# BQ76952_AFE.net
KiCad netlist of a schematic drawn in Altium Designer
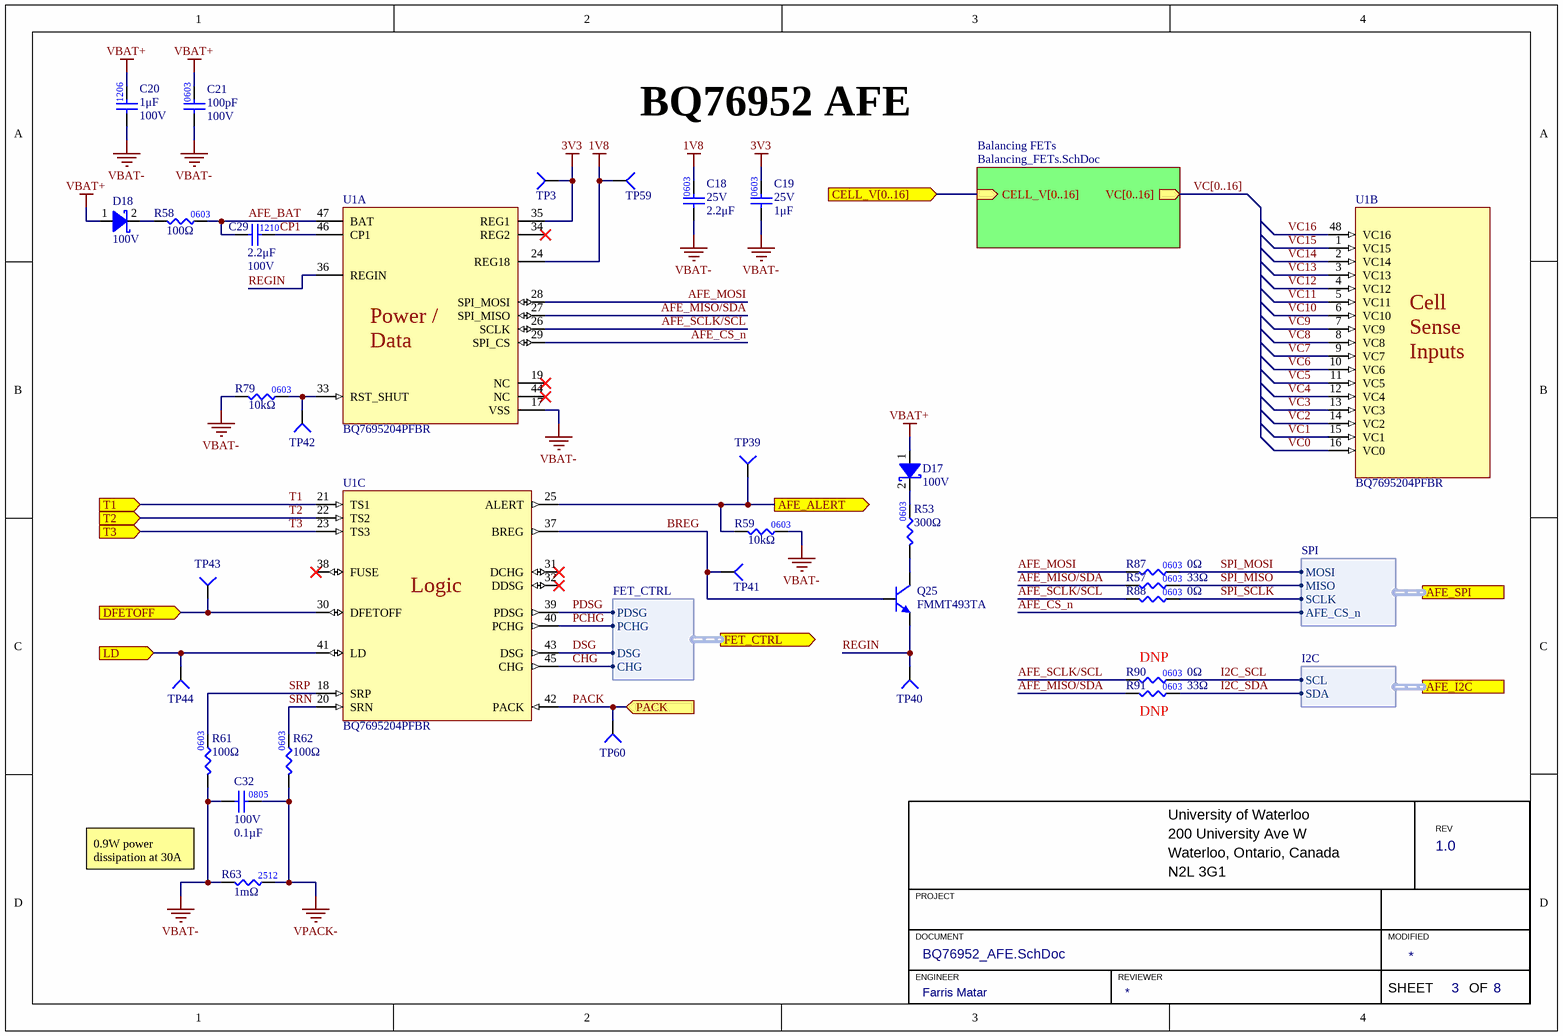
[diagram p0: BQ76952_AFE.SchDoc]

(export (version "E")
  (design (tool "Eeschema 10.0.6"))
  (components
    (comp (ref "C18")
      (value "2.2μF")
      (footprint "CAP0603")
      (description "CAP CER 2.2UF 25V X5R 0603")
      (fields (field (name "VOLTAGE RATING") "25V") (field (name "Comment") "CAP_2.2uF_25V_0603"))
      (libsource (lib "Personal_Schematic_Library_2022") (part "CAP_2.2uF_25V_0603"))
    )
    (comp (ref "C19")
      (value "1μF")
      (footprint "CAP0603")
      (description "CAP CER 1UF 25V X5R 0603")
      (fields (field (name "VOLTAGE RATING") "25V") (field (name "Comment") "CAP_1uF_25V_0603"))
      (libsource (lib "Personal_Schematic_Library_2022") (part "CAP_1uF_25V_0603"))
    )
    (comp (ref "C20")
      (value "1μF")
      (footprint "CAP1206")
      (description "CAP CER 1UF 100V X7R 1206")
      (fields (field (name "VOLTAGE RATING") "100V") (field (name "Comment") "CAP_1uF_100V_1206"))
      (libsource (lib "Personal_Schematic_Library_2022") (part "CAP_1uF_100V_1206"))
    )
    (comp (ref "C21")
      (value "100pF")
      (footprint "CAP2012")
      (description "CAP CER 100PF 100V X7R 0603")
      (fields (field (name "VOLTAGE RATING") "100V") (field (name "Comment") "CAP_100pF_100V_0603"))
      (libsource (lib "Personal_Schematic_Library_2022") (part "CAP_100pF_100V_0603"))
    )
    (comp (ref "C29")
      (value "2.2μF")
      (footprint "CAP1210")
      (description "CAP CER 2.2UF 100V X7R 1210")
      (fields (field (name "VOLTAGE RATING") "100V") (field (name "Comment") "CAP_2.2uF_100V_1210"))
      (libsource (lib "Personal_Schematic_Library_2022") (part "CAP_2.2uF_100V_1210"))
    )
    (comp (ref "C32")
      (value "0.1µF")
      (footprint "CAP0805")
      (description "CAP CER 0.1UF 100V X7R 0805")
      (fields (field (name "VOLTAGE RATING") "100V") (field (name "Comment") "CAP_0.1uF_100V_0805"))
      (libsource (lib "Personal_Schematic_Library_2022") (part "CAP_0.1uF_100V_0805"))
    )
    (comp (ref "D17")
      (value "DIO_SCHOTTKY_100V_1A")
      (footprint "SOD-123_FLAT")
      (description "DIODE SCHOTTKY 100V 1A SOD-123F")
      (fields (field (name "VR (MAX)") "100V"))
      (libsource (lib "Personal_Schematic_Library_2022") (part "DIO_SCHOTTKY_100V_1A"))
    )
    (comp (ref "D18")
      (value "DIO_SCHOTTKY_100V_1A")
      (footprint "SOD-123_FLAT")
      (description "DIODE SCHOTTKY 100V 1A SOD-123F")
      (fields (field (name "VR (MAX)") "100V"))
      (libsource (lib "Personal_Schematic_Library_2022") (part "DIO_SCHOTTKY_100V_1A"))
    )
    (comp (ref "Q25")
      (value "NPN_100V_1A")
      (footprint "SOT23-3")
      (description "TRANS NPN 100V 1A SOT23-3")
      (fields (field (name "MANUFACTURER PART NUMBER 1") "FMMT493TA"))
      (libsource (lib "Personal_Schematic_Library_2022") (part "NPN_100V_1A"))
    )
    (comp (ref "R53")
      (value "300Ω")
      (footprint "RES0603")
      (description "RES 200 OHM 1% 1/10W 0603")
      (fields (field (name "TOLERANCE") "1%") (field (name "Comment") "RES_300Ω_0603_1%"))
      (libsource (lib "Personal_Schematic_Library_2022") (part "RES_300Ω_0603_1%"))
    )
    (comp (ref "R57")
      (value "33Ω")
      (footprint "RES0603")
      (description "RES 33 OHM 1% 1/10W 0603")
      (fields (field (name "Comment") "RES_33Ω_0603_1%"))
      (libsource (lib "Personal_Schematic_Library_2022") (part "RES_33Ω_0603_1%"))
    )
    (comp (ref "R58")
      (value "100Ω")
      (footprint "RES0603")
      (description "RES 100 OHM 1% 1/10W 0603")
      (fields (field (name "Comment") "RES_100Ω_0603_1%"))
      (libsource (lib "Personal_Schematic_Library_2022") (part "RES_100Ω_0603_1%"))
    )
    (comp (ref "R59")
      (value "10kΩ")
      (footprint "RES0603")
      (description "RES 10K OHM 1% 1/8W 0603")
      (fields (field (name "Comment") "RES_10kΩ_0603_1%"))
      (libsource (lib "Personal_Schematic_Library_2022") (part "RES_10kΩ_0603_1%"))
    )
    (comp (ref "R61")
      (value "100Ω")
      (footprint "RES0603")
      (description "RES 100 OHM 1% 1/10W 0603")
      (fields (field (name "Comment") "RES_100Ω_0603_1%"))
      (libsource (lib "Personal_Schematic_Library_2022") (part "RES_100Ω_0603_1%"))
    )
    (comp (ref "R62")
      (value "100Ω")
      (footprint "RES0603")
      (description "RES 100 OHM 1% 1/10W 0603")
      (fields (field (name "Comment") "RES_100Ω_0603_1%"))
      (libsource (lib "Personal_Schematic_Library_2022") (part "RES_100Ω_0603_1%"))
    )
    (comp (ref "R63")
      (value "1mΩ")
      (footprint "RESC6532X75N")
      (description "RES 1 mOHM 1% 3W 2512")
      (fields (field (name "Comment") "RES_1mΩ_2512_1%"))
      (libsource (lib "Personal_Schematic_Library_2022") (part "RES_1mΩ_2512_1%"))
    )
    (comp (ref "R79")
      (value "10kΩ")
      (footprint "RES0603")
      (description "RES 10K OHM 1% 1/8W 0603")
      (fields (field (name "Comment") "RES_10kΩ_0603_1%"))
      (libsource (lib "Personal_Schematic_Library_2022") (part "RES_10kΩ_0603_1%"))
    )
    (comp (ref "R87")
      (value "0Ω")
      (footprint "RES0603")
      (description "RES 0 OHM JUMPER 1/10W 0603")
      (fields (field (name "Comment") "RES_0Ω_0603"))
      (libsource (lib "Personal_Schematic_Library_2022") (part "RES_0Ω_0603"))
    )
    (comp (ref "R88")
      (value "0Ω")
      (footprint "RES0603")
      (description "RES 0 OHM JUMPER 1/10W 0603")
      (fields (field (name "Comment") "RES_0Ω_0603"))
      (libsource (lib "Personal_Schematic_Library_2022") (part "RES_0Ω_0603"))
    )
    (comp (ref "R90")
      (value "0Ω")
      (footprint "RES0603")
      (description "RES 0 OHM JUMPER 1/10W 0603")
      (fields (field (name "Comment") "RES_0Ω_0603"))
      (libsource (lib "Personal_Schematic_Library_2022") (part "RES_0Ω_0603"))
    )
    (comp (ref "R91")
      (value "33Ω")
      (footprint "RES0603")
      (description "RES 33 OHM 1% 1/10W 0603")
      (fields (field (name "Comment") "RES_33Ω_0603_1%"))
      (libsource (lib "Personal_Schematic_Library_2022") (part "RES_33Ω_0603_1%"))
    )
    (comp (ref "TP3")
      (value "TESTPOINT_SMD_LOOP")
      (footprint "S1751-46R")
      (description "TESTPOINT SMD LOOP")
      (libsource (lib "UWRT_Schematic_Library_2020") (part "TESTPOINT_SMD_LOOP"))
    )
    (comp (ref "TP39")
      (value "TESTPOINT_1MM_CIRCLE")
      (footprint "TESTPOINT_CIRCLE_1MM")
      (description "TESTPOINT 1MM CIRCLE")
      (libsource (lib "Personal_Schematic_Library_2022") (part "TESTPOINT_1MM_CIRCLE"))
    )
    (comp (ref "TP40")
      (value "TESTPOINT_1MM_CIRCLE")
      (footprint "TESTPOINT_CIRCLE_1MM")
      (description "TESTPOINT 1MM CIRCLE")
      (libsource (lib "Personal_Schematic_Library_2022") (part "TESTPOINT_1MM_CIRCLE"))
    )
    (comp (ref "TP41")
      (value "TESTPOINT_1MM_CIRCLE")
      (footprint "TESTPOINT_CIRCLE_1MM")
      (description "TESTPOINT 1MM CIRCLE")
      (libsource (lib "Personal_Schematic_Library_2022") (part "TESTPOINT_1MM_CIRCLE"))
    )
    (comp (ref "TP42")
      (value "TESTPOINT_1MM_CIRCLE")
      (footprint "TESTPOINT_CIRCLE_1MM")
      (description "TESTPOINT 1MM CIRCLE")
      (libsource (lib "Personal_Schematic_Library_2022") (part "TESTPOINT_1MM_CIRCLE"))
    )
    (comp (ref "TP43")
      (value "TESTPOINT_1MM_CIRCLE")
      (footprint "TESTPOINT_CIRCLE_1MM")
      (description "TESTPOINT 1MM CIRCLE")
      (libsource (lib "Personal_Schematic_Library_2022") (part "TESTPOINT_1MM_CIRCLE"))
    )
    (comp (ref "TP44")
      (value "TESTPOINT_1MM_CIRCLE")
      (footprint "TESTPOINT_CIRCLE_1MM")
      (description "TESTPOINT 1MM CIRCLE")
      (libsource (lib "Personal_Schematic_Library_2022") (part "TESTPOINT_1MM_CIRCLE"))
    )
    (comp (ref "TP59")
      (value "TESTPOINT_1MM_SQUARE")
      (footprint "TESTPOINT_SQUARE_1MM")
      (description "TESTPOINT 1MM SQUARE")
      (libsource (lib "Personal_Schematic_Library_2022") (part "TESTPOINT_1MM_SQUARE"))
    )
    (comp (ref "TP60")
      (value "TESTPOINT_1MM_CIRCLE")
      (footprint "TESTPOINT_CIRCLE_1MM")
      (description "TESTPOINT 1MM CIRCLE")
      (libsource (lib "Personal_Schematic_Library_2022") (part "TESTPOINT_1MM_CIRCLE"))
    )
    (comp (ref "U1")
      (value "BQ7695204PFBR")
      (footprint "TI_48-TQFP")
      (description "IC BAT LIFEPO4/LI-ION 3-16C TQFP")
      (libsource (lib "Personal_Schematic_Library_2022") (part "BQ7695204PFBR"))
    )
  )
  (nets
    (net (code "21") (name "/AFE_ALERT") (class "Default")
      (node (ref "R59") (pin "1") (pinfunction "1_1") (pintype "passive"))
      (node (ref "TP39") (pin "1") (pinfunction "=value_1") (pintype "passive"))
      (node (ref "U1") (pin "25") (pinfunction "ALERT_25") (pintype "output"))
    )
    (net (code "22") (name "/AFE_BAT") (class "Default")
      (node (ref "C29") (pin "1") (pinfunction "1_1") (pintype "passive"))
      (node (ref "R58") (pin "2") (pinfunction "2_2") (pintype "passive"))
      (node (ref "U1") (pin "47") (pinfunction "BAT_47") (pintype "power_in"))
    )
    (net (code "23") (name "/AFE_CS_n") (class "Default")
      (node (ref "U1") (pin "29") (pinfunction "SPI_CS_29") (pintype "bidirectional"))
    )
    (net (code "24") (name "/AFE_MISO{slash}SDA") (class "Default")
      (node (ref "R57") (pin "1") (pinfunction "1_1") (pintype "passive"))
      (node (ref "R91") (pin "1") (pinfunction "1_1") (pintype "passive"))
      (node (ref "U1") (pin "27") (pinfunction "SPI_MISO_27") (pintype "bidirectional"))
    )
    (net (code "25") (name "/AFE_MOSI") (class "Default")
      (node (ref "R87") (pin "1") (pinfunction "1_1") (pintype "passive"))
      (node (ref "U1") (pin "28") (pinfunction "SPI_MOSI_28") (pintype "bidirectional"))
    )
    (net (code "26") (name "/AFE_SCLK{slash}SCL") (class "Default")
      (node (ref "R88") (pin "1") (pinfunction "1_1") (pintype "passive"))
      (node (ref "R90") (pin "1") (pinfunction "1_1") (pintype "passive"))
      (node (ref "U1") (pin "26") (pinfunction "SCLK_26") (pintype "bidirectional"))
    )
    (net (code "27") (name "/BREG") (class "Default")
      (node (ref "Q25") (pin "1") (pinfunction "B_1") (pintype "passive"))
      (node (ref "TP41") (pin "1") (pinfunction "=value_1") (pintype "passive"))
      (node (ref "U1") (pin "37") (pinfunction "BREG_37") (pintype "output"))
    )
    (net (code "29") (name "/CHG") (class "Default")
      (node (ref "U1") (pin "45") (pinfunction "CHG_45") (pintype "output"))
    )
    (net (code "30") (name "/CP1") (class "Default")
      (node (ref "C29") (pin "2") (pinfunction "2_2") (pintype "passive"))
      (node (ref "U1") (pin "46") (pinfunction "CP1_46") (pintype "power_in"))
    )
    (net (code "31") (name "/DFETOFF") (class "Default")
      (node (ref "TP43") (pin "1") (pinfunction "=value_1") (pintype "passive"))
      (node (ref "U1") (pin "30") (pinfunction "DFETOFF_30") (pintype "bidirectional"))
    )
    (net (code "32") (name "/DSG") (class "Default")
      (node (ref "U1") (pin "43") (pinfunction "DSG_43") (pintype "output"))
    )
    (net (code "33") (name "/I2C_SCL") (class "Default")
      (node (ref "R90") (pin "2") (pinfunction "2_2") (pintype "passive"))
    )
    (net (code "34") (name "/I2C_SDA") (class "Default")
      (node (ref "R91") (pin "2") (pinfunction "2_2") (pintype "passive"))
    )
    (net (code "35") (name "/LD") (class "Default")
      (node (ref "TP44") (pin "1") (pinfunction "=value_1") (pintype "passive"))
      (node (ref "U1") (pin "41") (pinfunction "LD_41") (pintype "bidirectional"))
    )
    (net (code "36") (name "/PACK") (class "Default")
      (node (ref "TP60") (pin "1") (pinfunction "=value_1") (pintype "passive"))
      (node (ref "U1") (pin "42") (pinfunction "PACK_42") (pintype "input"))
    )
    (net (code "37") (name "/PCHG") (class "Default")
      (node (ref "U1") (pin "40") (pinfunction "PCHG_40") (pintype "output"))
    )
    (net (code "38") (name "/PDSG") (class "Default")
      (node (ref "U1") (pin "39") (pinfunction "PDSG_39") (pintype "output"))
    )
    (net (code "39") (name "/REGIN") (class "Default")
      (node (ref "Q25") (pin "2") (pinfunction "E_2") (pintype "passive"))
      (node (ref "TP40") (pin "1") (pinfunction "=value_1") (pintype "passive"))
      (node (ref "U1") (pin "36") (pinfunction "REGIN_36") (pintype "power_in"))
    )
    (net (code "40") (name "/SPI_MISO") (class "Default")
      (node (ref "R57") (pin "2") (pinfunction "2_2") (pintype "passive"))
    )
    (net (code "41") (name "/SPI_MOSI") (class "Default")
      (node (ref "R87") (pin "2") (pinfunction "2_2") (pintype "passive"))
    )
    (net (code "42") (name "/SPI_SCLK") (class "Default")
      (node (ref "R88") (pin "2") (pinfunction "2_2") (pintype "passive"))
    )
    (net (code "43") (name "/SRN") (class "Default")
      (node (ref "R62") (pin "2") (pinfunction "2_2") (pintype "passive"))
      (node (ref "U1") (pin "20") (pinfunction "SRN_20") (pintype "input"))
    )
    (net (code "44") (name "/SRP") (class "Default")
      (node (ref "R61") (pin "2") (pinfunction "2_2") (pintype "passive"))
      (node (ref "U1") (pin "18") (pinfunction "SRP_18") (pintype "input"))
    )
    (net (code "45") (name "/T1") (class "Default")
      (node (ref "U1") (pin "21") (pinfunction "TS1_21") (pintype "input"))
    )
    (net (code "46") (name "/T2") (class "Default")
      (node (ref "U1") (pin "22") (pinfunction "TS2_22") (pintype "input"))
    )
    (net (code "47") (name "/T3") (class "Default")
      (node (ref "U1") (pin "23") (pinfunction "TS3_23") (pintype "input"))
    )
    (net (code "48") (name "/VC0") (class "Default")
      (node (ref "U1") (pin "16") (pinfunction "VC0_16") (pintype "input"))
    )
    (net (code "49") (name "/VC1") (class "Default")
      (node (ref "U1") (pin "15") (pinfunction "VC1_15") (pintype "input"))
    )
    (net (code "50") (name "/VC2") (class "Default")
      (node (ref "U1") (pin "14") (pinfunction "VC2_14") (pintype "input"))
    )
    (net (code "51") (name "/VC3") (class "Default")
      (node (ref "U1") (pin "13") (pinfunction "VC3_13") (pintype "input"))
    )
    (net (code "52") (name "/VC4") (class "Default")
      (node (ref "U1") (pin "12") (pinfunction "VC4_12") (pintype "input"))
    )
    (net (code "53") (name "/VC5") (class "Default")
      (node (ref "U1") (pin "11") (pinfunction "VC5_11") (pintype "input"))
    )
    (net (code "54") (name "/VC6") (class "Default")
      (node (ref "U1") (pin "10") (pinfunction "VC6_10") (pintype "input"))
    )
    (net (code "55") (name "/VC7") (class "Default")
      (node (ref "U1") (pin "9") (pinfunction "VC7_9") (pintype "input"))
    )
    (net (code "56") (name "/VC8") (class "Default")
      (node (ref "U1") (pin "8") (pinfunction "VC8_8") (pintype "input"))
    )
    (net (code "57") (name "/VC9") (class "Default")
      (node (ref "U1") (pin "7") (pinfunction "VC9_7") (pintype "input"))
    )
    (net (code "58") (name "/VC10") (class "Default")
      (node (ref "U1") (pin "6") (pinfunction "VC10_6") (pintype "input"))
    )
    (net (code "59") (name "/VC11") (class "Default")
      (node (ref "U1") (pin "5") (pinfunction "VC11_5") (pintype "input"))
    )
    (net (code "60") (name "/VC12") (class "Default")
      (node (ref "U1") (pin "4") (pinfunction "VC12_4") (pintype "input"))
    )
    (net (code "61") (name "/VC13") (class "Default")
      (node (ref "U1") (pin "3") (pinfunction "VC13_3") (pintype "input"))
    )
    (net (code "62") (name "/VC14") (class "Default")
      (node (ref "U1") (pin "2") (pinfunction "VC14_2") (pintype "input"))
    )
    (net (code "63") (name "/VC15") (class "Default")
      (node (ref "U1") (pin "1") (pinfunction "VC15_1") (pintype "input"))
    )
    (net (code "64") (name "/VC16") (class "Default")
      (node (ref "U1") (pin "48") (pinfunction "VC16_48") (pintype "input"))
    )
    (net (code "69") (name "1V8") (class "Default")
      (node (ref "C18") (pin "2") (pinfunction "2_2") (pintype "passive"))
      (node (ref "TP59") (pin "1") (pinfunction "=value_1") (pintype "passive"))
      (node (ref "U1") (pin "24") (pinfunction "REG18_24") (pintype "power_in"))
    )
    (net (code "70") (name "3V3") (class "Default")
      (node (ref "C19") (pin "2") (pinfunction "2_2") (pintype "passive"))
      (node (ref "TP3") (pin "1") (pinfunction "=value_1") (pintype "passive"))
      (node (ref "U1") (pin "35") (pinfunction "REG1_35") (pintype "power_in"))
    )
    (net (code "71") (name "Net-(D17-Cathode)") (class "Default")
      (node (ref "D17") (pin "2") (pinfunction "Cathode_2") (pintype "passive"))
      (node (ref "R53") (pin "2") (pinfunction "2_2") (pintype "passive"))
    )
    (net (code "72") (name "Net-(D18-Cathode)") (class "Default")
      (node (ref "D18") (pin "2") (pinfunction "Cathode_2") (pintype "passive"))
      (node (ref "R58") (pin "1") (pinfunction "1_1") (pintype "passive"))
    )
    (net (code "73") (name "Net-(Q25-C)") (class "Default")
      (node (ref "Q25") (pin "3") (pinfunction "C_3") (pintype "passive"))
      (node (ref "R53") (pin "1") (pinfunction "1_1") (pintype "passive"))
    )
    (net (code "74") (name "Net-(TP42-=value)") (class "Default")
      (node (ref "R79") (pin "2") (pinfunction "2_2") (pintype "passive"))
      (node (ref "TP42") (pin "1") (pinfunction "=value_1") (pintype "passive"))
      (node (ref "U1") (pin "33") (pinfunction "RST_SHUT_33") (pintype "input"))
    )
    (net (code "75") (name "VBAT+") (class "Default")
      (node (ref "C20") (pin "2") (pinfunction "2_2") (pintype "passive"))
      (node (ref "C21") (pin "2") (pinfunction "2_2") (pintype "passive"))
      (node (ref "D17") (pin "1") (pinfunction "Anode_1") (pintype "passive"))
      (node (ref "D18") (pin "1") (pinfunction "Anode_1") (pintype "passive"))
    )
    (net (code "76") (name "VBAT-") (class "Default")
      (node (ref "C18") (pin "1") (pinfunction "1_1") (pintype "passive"))
      (node (ref "C19") (pin "1") (pinfunction "1_1") (pintype "passive"))
      (node (ref "C20") (pin "1") (pinfunction "1_1") (pintype "passive"))
      (node (ref "C21") (pin "1") (pinfunction "1_1") (pintype "passive"))
      (node (ref "C32") (pin "1") (pinfunction "1_1") (pintype "passive"))
      (node (ref "R59") (pin "2") (pinfunction "2_2") (pintype "passive"))
      (node (ref "R61") (pin "1") (pinfunction "1_1") (pintype "passive"))
      (node (ref "R63") (pin "1") (pinfunction "1_1") (pintype "passive"))
      (node (ref "R79") (pin "1") (pinfunction "1_1") (pintype "passive"))
      (node (ref "U1") (pin "17") (pinfunction "VSS_17") (pintype "power_in"))
    )
    (net (code "77") (name "VPACK-") (class "Default")
      (node (ref "C32") (pin "2") (pinfunction "2_2") (pintype "passive"))
      (node (ref "R62") (pin "1") (pinfunction "1_1") (pintype "passive"))
      (node (ref "R63") (pin "2") (pinfunction "2_2") (pintype "passive"))
    )
    (net (code "78") (name "unconnected-(U1A-NC-Pad19)") (class "Default")
      (node (ref "U1") (pin "19") (pinfunction "NC_19") (pintype "passive+no_connect"))
    )
    (net (code "79") (name "unconnected-(U1A-NC-Pad44)") (class "Default")
      (node (ref "U1") (pin "44") (pinfunction "NC_44") (pintype "passive+no_connect"))
    )
    (net (code "80") (name "unconnected-(U1A-REG2-Pad34)") (class "Default")
      (node (ref "U1") (pin "34") (pinfunction "REG2_34") (pintype "power_in+no_connect"))
    )
    (net (code "81") (name "unconnected-(U1C-DCHG-Pad31)") (class "Default")
      (node (ref "U1") (pin "31") (pinfunction "DCHG_31") (pintype "bidirectional+no_connect"))
    )
    (net (code "82") (name "unconnected-(U1C-DDSG-Pad32)") (class "Default")
      (node (ref "U1") (pin "32") (pinfunction "DDSG_32") (pintype "bidirectional+no_connect"))
    )
    (net (code "83") (name "unconnected-(U1C-FUSE-Pad38)") (class "Default")
      (node (ref "U1") (pin "38") (pinfunction "FUSE_38") (pintype "bidirectional+no_connect"))
    )
  )
)
